# SCREEN.net
KiCad netlist of a schematic drawn in Altium Designer
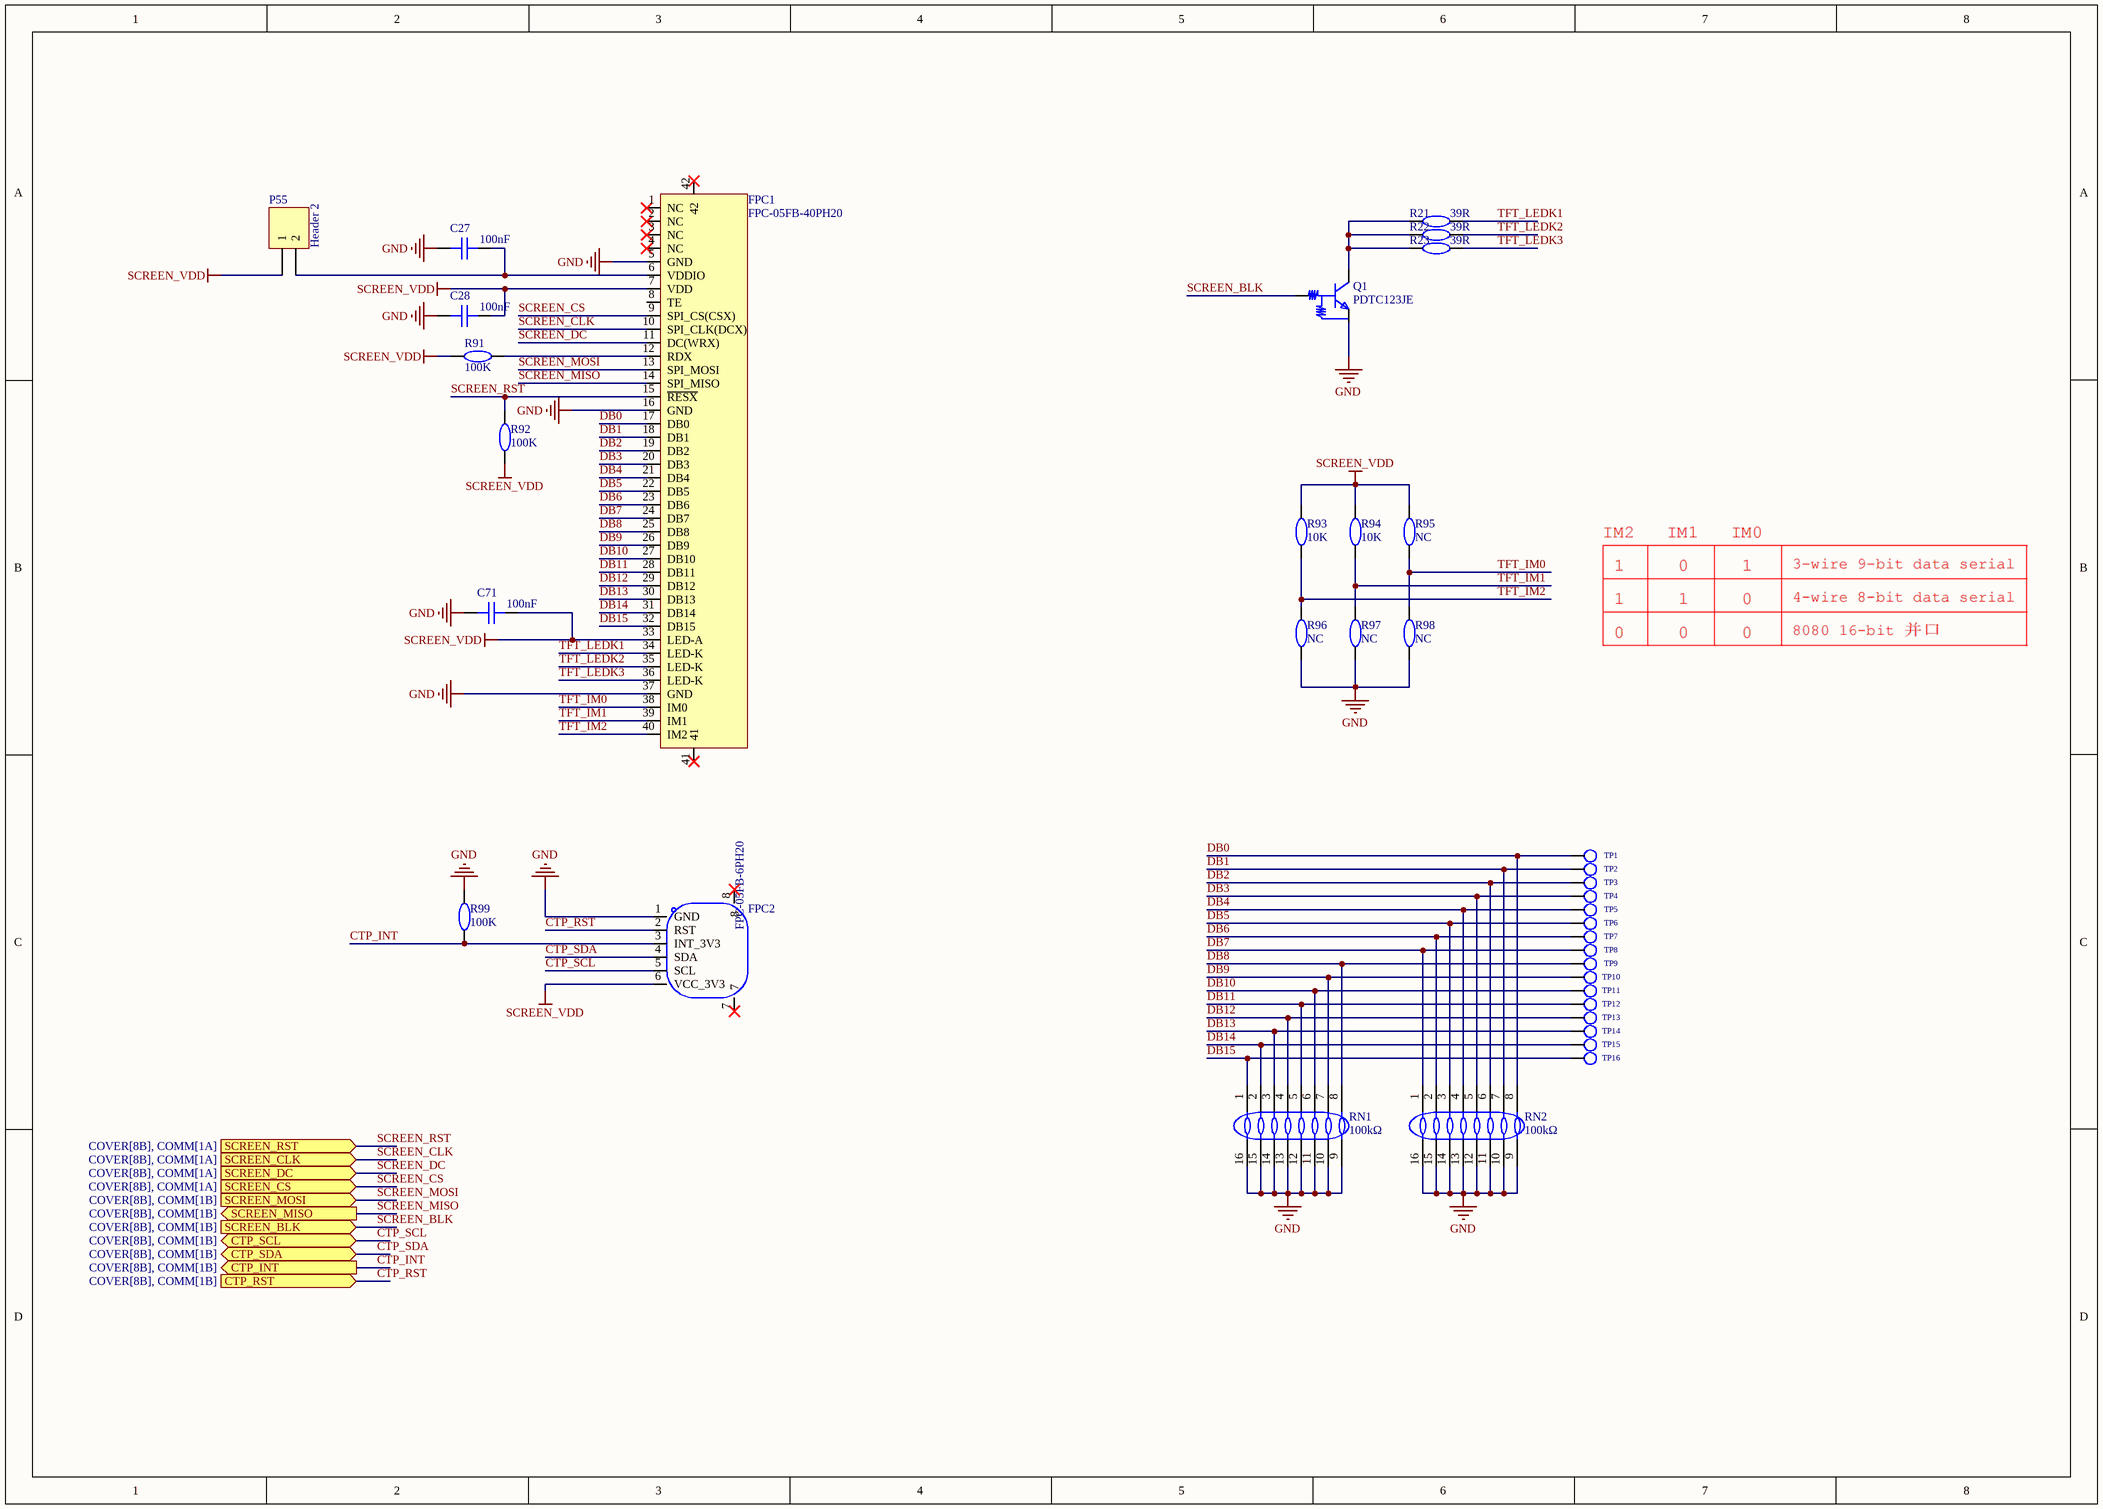
[diagram p0: SCREEN.SchDoc]

(export (version "E")
  (design (tool "Eeschema 10.0.6"))
  (components
    (comp (ref "C27")
      (value "100nF")
      (footprint "C0402")
      (fields (field (name "NAME") "100nF"))
      (libsource (lib "my_library") (part "CAP_0402"))
    )
    (comp (ref "C28")
      (value "100nF")
      (footprint "C0402")
      (fields (field (name "NAME") "100nF"))
      (libsource (lib "my_library") (part "CAP_0402"))
    )
    (comp (ref "C71")
      (value "100nF")
      (footprint "C0402")
      (fields (field (name "NAME") "100nF"))
      (libsource (lib "my_library") (part "CAP_0402"))
    )
    (comp (ref "FPC1")
      (value "FPC-05FB-40PH20")
      (footprint "FPC-SMD_40P-P0.50_XUNPU_FPC-05FB-40PH20")
      (fields (field (name "MANUFACTURER") "XUNPU(讯普)") (field (name "NAME") "FPC-05FB-40PH20"))
      (libsource (lib "my_library") (part "3.2TFT_FPC-05FB-40PH20"))
    )
    (comp (ref "FPC2")
      (value "FPC-05FB-6PH20")
      (footprint "FPC-SMD_6P-P0.50_FPC-05FB-6PH20")
      (fields (field (name "MANUFACTURER") "XUNPU(讯普)") (field (name "NAME") "FPC-05FB-6PH20"))
      (libsource (lib "my_library") (part "3.2TFT_FPC-05FB-6PH20"))
    )
    (comp (ref "P55")
      (value "Header 2")
      (footprint "HDR1X2")
      (description "Header, 2-Pin")
      (fields (field (name "PUBLISHER") "Altium Limited"))
      (libsource (lib "Miscellaneous Connectors") (part "Header 2"))
    )
    (comp (ref "Q1")
      (value "PDTC123JE")
      (footprint "SOT-523_L1.6-W0.8-P1.00-LS1.6-BR")
      (fields (field (name "MANUFACTURER") "Prisemi(芯导)") (field (name "NAME") "PDTC123JE"))
      (libsource (lib "my_library") (part "PDTC123JE"))
    )
    (comp (ref "R21")
      (value "39R")
      (footprint "R0402")
      (fields (field (name "NAME") "39R"))
      (libsource (lib "my_library") (part "Res_0402"))
    )
    (comp (ref "R22")
      (value "39R")
      (footprint "R0402")
      (fields (field (name "NAME") "39R"))
      (libsource (lib "my_library") (part "Res_0402"))
    )
    (comp (ref "R23")
      (value "39R")
      (footprint "R0402")
      (fields (field (name "NAME") "39R"))
      (libsource (lib "my_library") (part "Res_0402"))
    )
    (comp (ref "R91")
      (value "100K")
      (footprint "R0402")
      (fields (field (name "NAME") "100K"))
      (libsource (lib "my_library") (part "Res_0402"))
    )
    (comp (ref "R92")
      (value "100K")
      (footprint "R0402")
      (fields (field (name "NAME") "100K"))
      (libsource (lib "my_library") (part "Res_0402"))
    )
    (comp (ref "R93")
      (value "10K")
      (footprint "R0603")
      (fields (field (name "NAME") "10K"))
      (libsource (lib "my_library") (part "Res_0603"))
    )
    (comp (ref "R94")
      (value "10K")
      (footprint "R0603")
      (fields (field (name "NAME") "10K"))
      (libsource (lib "my_library") (part "Res_0603"))
    )
    (comp (ref "R95")
      (value "NC")
      (footprint "R0603")
      (fields (field (name "NAME") "NC"))
      (libsource (lib "my_library") (part "Res_0603"))
    )
    (comp (ref "R96")
      (value "NC")
      (footprint "R0603")
      (fields (field (name "NAME") "NC"))
      (libsource (lib "my_library") (part "Res_0603"))
    )
    (comp (ref "R97")
      (value "NC")
      (footprint "R0603")
      (fields (field (name "NAME") "NC"))
      (libsource (lib "my_library") (part "Res_0603"))
    )
    (comp (ref "R98")
      (value "NC")
      (footprint "R0603")
      (fields (field (name "NAME") "NC"))
      (libsource (lib "my_library") (part "Res_0603"))
    )
    (comp (ref "R99")
      (value "100K")
      (footprint "R0402")
      (fields (field (name "NAME") "100K"))
      (libsource (lib "my_library") (part "Res_0402"))
    )
    (comp (ref "RN1")
      (value "100kΩ")
      (footprint "RES-ARRAY-SMD_16P-L3.8-W1.6-P0.50-BL")
      (fields
        (field (name "MANUFACTURER") "PANASONIC(松下)")
        (field (name "MANUFACTURER PART") "EXB2HV104JV")
        (field (name "TOLERANCE") "±5%")
        (field (name "NAME") "100kΩ")
      )
      (libsource (lib "my_library") (part "EXB2HV104JV"))
    )
    (comp (ref "RN2")
      (value "100kΩ")
      (footprint "RES-ARRAY-SMD_16P-L3.8-W1.6-P0.50-BL")
      (fields
        (field (name "MANUFACTURER") "PANASONIC(松下)")
        (field (name "MANUFACTURER PART") "EXB2HV104JV")
        (field (name "TOLERANCE") "±5%")
        (field (name "NAME") "100kΩ")
      )
      (libsource (lib "my_library") (part "EXB2HV104JV"))
    )
    (comp (ref "TP1")
      (value "T-SMD")
      (footprint "PAD_1.0_SMT")
      (libsource (lib "my_library") (part "T1.0-SMD"))
    )
    (comp (ref "TP2")
      (value "T-SMD")
      (footprint "PAD_1.0_SMT")
      (libsource (lib "my_library") (part "T1.0-SMD"))
    )
    (comp (ref "TP3")
      (value "T-SMD")
      (footprint "PAD_1.0_SMT")
      (libsource (lib "my_library") (part "T1.0-SMD"))
    )
    (comp (ref "TP4")
      (value "T-SMD")
      (footprint "PAD_1.0_SMT")
      (libsource (lib "my_library") (part "T1.0-SMD"))
    )
    (comp (ref "TP5")
      (value "T-SMD")
      (footprint "PAD_1.0_SMT")
      (libsource (lib "my_library") (part "T1.0-SMD"))
    )
    (comp (ref "TP6")
      (value "T-SMD")
      (footprint "PAD_1.0_SMT")
      (libsource (lib "my_library") (part "T1.0-SMD"))
    )
    (comp (ref "TP7")
      (value "T-SMD")
      (footprint "PAD_1.0_SMT")
      (libsource (lib "my_library") (part "T1.0-SMD"))
    )
    (comp (ref "TP8")
      (value "T-SMD")
      (footprint "PAD_1.0_SMT")
      (libsource (lib "my_library") (part "T1.0-SMD"))
    )
    (comp (ref "TP9")
      (value "T-SMD")
      (footprint "PAD_1.0_SMT")
      (libsource (lib "my_library") (part "T1.0-SMD"))
    )
    (comp (ref "TP10")
      (value "T-SMD")
      (footprint "PAD_1.0_SMT")
      (libsource (lib "my_library") (part "T1.0-SMD"))
    )
    (comp (ref "TP11")
      (value "T-SMD")
      (footprint "PAD_1.0_SMT")
      (libsource (lib "my_library") (part "T1.0-SMD"))
    )
    (comp (ref "TP12")
      (value "T-SMD")
      (footprint "PAD_1.0_SMT")
      (libsource (lib "my_library") (part "T1.0-SMD"))
    )
    (comp (ref "TP13")
      (value "T-SMD")
      (footprint "PAD_1.0_SMT")
      (libsource (lib "my_library") (part "T1.0-SMD"))
    )
    (comp (ref "TP14")
      (value "T-SMD")
      (footprint "PAD_1.0_SMT")
      (libsource (lib "my_library") (part "T1.0-SMD"))
    )
    (comp (ref "TP15")
      (value "T-SMD")
      (footprint "PAD_1.0_SMT")
      (libsource (lib "my_library") (part "T1.0-SMD"))
    )
    (comp (ref "TP16")
      (value "T-SMD")
      (footprint "PAD_1.0_SMT")
      (libsource (lib "my_library") (part "T1.0-SMD"))
    )
  )
  (nets
    (net (code "1") (name "/CTP_INT") (class "Default")
      (node (ref "FPC2") (pin "3") (pinfunction "INT_3V3_3") (pintype "passive"))
      (node (ref "R99") (pin "2") (pinfunction "2_2") (pintype "passive"))
    )
    (net (code "2") (name "/CTP_RST") (class "Default")
      (node (ref "FPC2") (pin "2") (pinfunction "RST_2") (pintype "passive"))
    )
    (net (code "3") (name "/CTP_SCL") (class "Default")
      (node (ref "FPC2") (pin "5") (pinfunction "SCL_5") (pintype "passive"))
    )
    (net (code "4") (name "/CTP_SDA") (class "Default")
      (node (ref "FPC2") (pin "4") (pinfunction "SDA_4") (pintype "passive"))
    )
    (net (code "5") (name "/DB0") (class "Default")
      (node (ref "FPC1") (pin "17") (pinfunction "DB0_17") (pintype "passive"))
      (node (ref "RN2") (pin "8") (pinfunction "8_8") (pintype "passive"))
      (node (ref "TP1") (pin "1") (pinfunction "1_1") (pintype "passive"))
    )
    (net (code "6") (name "/DB1") (class "Default")
      (node (ref "FPC1") (pin "18") (pinfunction "DB1_18") (pintype "passive"))
      (node (ref "RN2") (pin "7") (pinfunction "7_7") (pintype "passive"))
      (node (ref "TP2") (pin "1") (pinfunction "1_1") (pintype "passive"))
    )
    (net (code "7") (name "/DB2") (class "Default")
      (node (ref "FPC1") (pin "19") (pinfunction "DB2_19") (pintype "passive"))
      (node (ref "RN2") (pin "6") (pinfunction "6_6") (pintype "passive"))
      (node (ref "TP3") (pin "1") (pinfunction "1_1") (pintype "passive"))
    )
    (net (code "8") (name "/DB3") (class "Default")
      (node (ref "FPC1") (pin "20") (pinfunction "DB3_20") (pintype "passive"))
      (node (ref "RN2") (pin "5") (pinfunction "5_5") (pintype "passive"))
      (node (ref "TP4") (pin "1") (pinfunction "1_1") (pintype "passive"))
    )
    (net (code "9") (name "/DB4") (class "Default")
      (node (ref "FPC1") (pin "21") (pinfunction "DB4_21") (pintype "passive"))
      (node (ref "RN2") (pin "4") (pinfunction "4_4") (pintype "passive"))
      (node (ref "TP5") (pin "1") (pinfunction "1_1") (pintype "passive"))
    )
    (net (code "10") (name "/DB5") (class "Default")
      (node (ref "FPC1") (pin "22") (pinfunction "DB5_22") (pintype "passive"))
      (node (ref "RN2") (pin "3") (pinfunction "3_3") (pintype "passive"))
      (node (ref "TP6") (pin "1") (pinfunction "1_1") (pintype "passive"))
    )
    (net (code "11") (name "/DB6") (class "Default")
      (node (ref "FPC1") (pin "23") (pinfunction "DB6_23") (pintype "passive"))
      (node (ref "RN2") (pin "2") (pinfunction "2_2") (pintype "passive"))
      (node (ref "TP7") (pin "1") (pinfunction "1_1") (pintype "passive"))
    )
    (net (code "12") (name "/DB7") (class "Default")
      (node (ref "FPC1") (pin "24") (pinfunction "DB7_24") (pintype "passive"))
      (node (ref "RN2") (pin "1") (pinfunction "1_1") (pintype "passive"))
      (node (ref "TP8") (pin "1") (pinfunction "1_1") (pintype "passive"))
    )
    (net (code "13") (name "/DB8") (class "Default")
      (node (ref "FPC1") (pin "25") (pinfunction "DB8_25") (pintype "passive"))
      (node (ref "RN1") (pin "8") (pinfunction "8_8") (pintype "passive"))
      (node (ref "TP9") (pin "1") (pinfunction "1_1") (pintype "passive"))
    )
    (net (code "14") (name "/DB9") (class "Default")
      (node (ref "FPC1") (pin "26") (pinfunction "DB9_26") (pintype "passive"))
      (node (ref "RN1") (pin "7") (pinfunction "7_7") (pintype "passive"))
      (node (ref "TP10") (pin "1") (pinfunction "1_1") (pintype "passive"))
    )
    (net (code "15") (name "/DB10") (class "Default")
      (node (ref "FPC1") (pin "27") (pinfunction "DB10_27") (pintype "passive"))
      (node (ref "RN1") (pin "6") (pinfunction "6_6") (pintype "passive"))
      (node (ref "TP11") (pin "1") (pinfunction "1_1") (pintype "passive"))
    )
    (net (code "16") (name "/DB11") (class "Default")
      (node (ref "FPC1") (pin "28") (pinfunction "DB11_28") (pintype "passive"))
      (node (ref "RN1") (pin "5") (pinfunction "5_5") (pintype "passive"))
      (node (ref "TP12") (pin "1") (pinfunction "1_1") (pintype "passive"))
    )
    (net (code "17") (name "/DB12") (class "Default")
      (node (ref "FPC1") (pin "29") (pinfunction "DB12_29") (pintype "passive"))
      (node (ref "RN1") (pin "4") (pinfunction "4_4") (pintype "passive"))
      (node (ref "TP13") (pin "1") (pinfunction "1_1") (pintype "passive"))
    )
    (net (code "18") (name "/DB13") (class "Default")
      (node (ref "FPC1") (pin "30") (pinfunction "DB13_30") (pintype "passive"))
      (node (ref "RN1") (pin "3") (pinfunction "3_3") (pintype "passive"))
      (node (ref "TP14") (pin "1") (pinfunction "1_1") (pintype "passive"))
    )
    (net (code "19") (name "/DB14") (class "Default")
      (node (ref "FPC1") (pin "31") (pinfunction "DB14_31") (pintype "passive"))
      (node (ref "RN1") (pin "2") (pinfunction "2_2") (pintype "passive"))
      (node (ref "TP15") (pin "1") (pinfunction "1_1") (pintype "passive"))
    )
    (net (code "20") (name "/DB15") (class "Default")
      (node (ref "FPC1") (pin "32") (pinfunction "DB15_32") (pintype "passive"))
      (node (ref "RN1") (pin "1") (pinfunction "1_1") (pintype "passive"))
      (node (ref "TP16") (pin "1") (pinfunction "1_1") (pintype "passive"))
    )
    (net (code "21") (name "/SCREEN_BLK") (class "Default")
      (node (ref "Q1") (pin "1") (pinfunction "IN_1") (pintype "passive"))
    )
    (net (code "22") (name "/SCREEN_CLK") (class "Default")
      (node (ref "FPC1") (pin "10") (pinfunction "SPI_CLK(DCX)_10") (pintype "passive"))
    )
    (net (code "23") (name "/SCREEN_CS") (class "Default")
      (node (ref "FPC1") (pin "9") (pinfunction "SPI_CS(CSX)_9") (pintype "passive"))
    )
    (net (code "24") (name "/SCREEN_DC") (class "Default")
      (node (ref "FPC1") (pin "11") (pinfunction "DC(WRX)_11") (pintype "passive"))
    )
    (net (code "25") (name "/SCREEN_MISO") (class "Default")
      (node (ref "FPC1") (pin "14") (pinfunction "SPI_MISO_14") (pintype "passive"))
    )
    (net (code "26") (name "/SCREEN_MOSI") (class "Default")
      (node (ref "FPC1") (pin "13") (pinfunction "SPI_MOSI_13") (pintype "passive"))
    )
    (net (code "27") (name "/SCREEN_RST") (class "Default")
      (node (ref "FPC1") (pin "15") (pinfunction "~{RESX}_15") (pintype "passive"))
      (node (ref "R92") (pin "2") (pinfunction "2_2") (pintype "passive"))
    )
    (net (code "28") (name "/TFT_IM0") (class "Default")
      (node (ref "FPC1") (pin "38") (pinfunction "IM0_38") (pintype "passive"))
      (node (ref "R95") (pin "1") (pinfunction "1_1") (pintype "passive"))
      (node (ref "R98") (pin "2") (pinfunction "2_2") (pintype "passive"))
    )
    (net (code "29") (name "/TFT_IM1") (class "Default")
      (node (ref "FPC1") (pin "39") (pinfunction "IM1_39") (pintype "passive"))
      (node (ref "R94") (pin "1") (pinfunction "1_1") (pintype "passive"))
      (node (ref "R97") (pin "2") (pinfunction "2_2") (pintype "passive"))
    )
    (net (code "30") (name "/TFT_IM2") (class "Default")
      (node (ref "FPC1") (pin "40") (pinfunction "IM2_40") (pintype "passive"))
      (node (ref "R93") (pin "1") (pinfunction "1_1") (pintype "passive"))
      (node (ref "R96") (pin "2") (pinfunction "2_2") (pintype "passive"))
    )
    (net (code "31") (name "/TFT_LEDK1") (class "Default")
      (node (ref "FPC1") (pin "34") (pinfunction "LED-K_34") (pintype "passive"))
      (node (ref "R21") (pin "2") (pinfunction "2_2") (pintype "passive"))
    )
    (net (code "32") (name "/TFT_LEDK2") (class "Default")
      (node (ref "FPC1") (pin "35") (pinfunction "LED-K_35") (pintype "passive"))
      (node (ref "R22") (pin "2") (pinfunction "2_2") (pintype "passive"))
    )
    (net (code "33") (name "/TFT_LEDK3") (class "Default")
      (node (ref "FPC1") (pin "36") (pinfunction "LED-K_36") (pintype "passive"))
      (node (ref "R23") (pin "2") (pinfunction "2_2") (pintype "passive"))
    )
    (net (code "34") (name "GND") (class "Default")
      (node (ref "C27") (pin "1") (pinfunction "1_1") (pintype "passive"))
      (node (ref "C28") (pin "1") (pinfunction "1_1") (pintype "passive"))
      (node (ref "C71") (pin "1") (pinfunction "1_1") (pintype "passive"))
      (node (ref "FPC1") (pin "16") (pinfunction "GND_16") (pintype "passive"))
      (node (ref "FPC1") (pin "37") (pinfunction "GND_37") (pintype "passive"))
      (node (ref "FPC1") (pin "5") (pinfunction "GND_5") (pintype "passive"))
      (node (ref "FPC2") (pin "1") (pinfunction "GND_1") (pintype "passive"))
      (node (ref "Q1") (pin "2") (pinfunction "GND_2") (pintype "passive"))
      (node (ref "R96") (pin "1") (pinfunction "1_1") (pintype "passive"))
      (node (ref "R97") (pin "1") (pinfunction "1_1") (pintype "passive"))
      (node (ref "R98") (pin "1") (pinfunction "1_1") (pintype "passive"))
      (node (ref "R99") (pin "1") (pinfunction "1_1") (pintype "passive"))
      (node (ref "RN1") (pin "10") (pinfunction "10_10") (pintype "passive"))
      (node (ref "RN1") (pin "11") (pinfunction "11_11") (pintype "passive"))
      (node (ref "RN1") (pin "12") (pinfunction "12_12") (pintype "passive"))
      (node (ref "RN1") (pin "13") (pinfunction "13_13") (pintype "passive"))
      (node (ref "RN1") (pin "14") (pinfunction "14_14") (pintype "passive"))
      (node (ref "RN1") (pin "15") (pinfunction "15_15") (pintype "passive"))
      (node (ref "RN1") (pin "16") (pinfunction "16_16") (pintype "passive"))
      (node (ref "RN1") (pin "9") (pinfunction "9_9") (pintype "passive"))
      (node (ref "RN2") (pin "10") (pinfunction "10_10") (pintype "passive"))
      (node (ref "RN2") (pin "11") (pinfunction "11_11") (pintype "passive"))
      (node (ref "RN2") (pin "12") (pinfunction "12_12") (pintype "passive"))
      (node (ref "RN2") (pin "13") (pinfunction "13_13") (pintype "passive"))
      (node (ref "RN2") (pin "14") (pinfunction "14_14") (pintype "passive"))
      (node (ref "RN2") (pin "15") (pinfunction "15_15") (pintype "passive"))
      (node (ref "RN2") (pin "16") (pinfunction "16_16") (pintype "passive"))
      (node (ref "RN2") (pin "9") (pinfunction "9_9") (pintype "passive"))
    )
    (net (code "35") (name "Net-(FPC1-RDX)") (class "Default")
      (node (ref "FPC1") (pin "12") (pinfunction "RDX_12") (pintype "passive"))
      (node (ref "R91") (pin "2") (pinfunction "2_2") (pintype "passive"))
    )
    (net (code "36") (name "Net-(FPC1-VDDIO)") (class "Default")
      (node (ref "C27") (pin "2") (pinfunction "2_2") (pintype "passive"))
      (node (ref "FPC1") (pin "6") (pinfunction "VDDIO_6") (pintype "passive"))
      (node (ref "P55") (pin "2") (pinfunction "2_2") (pintype "passive"))
    )
    (net (code "37") (name "Net-(Q1-OUT)") (class "Default")
      (node (ref "Q1") (pin "3") (pinfunction "OUT_3") (pintype "passive"))
      (node (ref "R21") (pin "1") (pinfunction "1_1") (pintype "passive"))
      (node (ref "R22") (pin "1") (pinfunction "1_1") (pintype "passive"))
      (node (ref "R23") (pin "1") (pinfunction "1_1") (pintype "passive"))
    )
    (net (code "38") (name "SCREEN_VDD") (class "Default")
      (node (ref "C28") (pin "2") (pinfunction "2_2") (pintype "passive"))
      (node (ref "C71") (pin "2") (pinfunction "2_2") (pintype "passive"))
      (node (ref "FPC1") (pin "33") (pinfunction "LED-A_33") (pintype "passive"))
      (node (ref "FPC1") (pin "7") (pinfunction "VDD_7") (pintype "passive"))
      (node (ref "FPC2") (pin "6") (pinfunction "VCC_3V3_6") (pintype "passive"))
      (node (ref "P55") (pin "1") (pinfunction "1_1") (pintype "passive"))
      (node (ref "R91") (pin "1") (pinfunction "1_1") (pintype "passive"))
      (node (ref "R92") (pin "1") (pinfunction "1_1") (pintype "passive"))
      (node (ref "R93") (pin "2") (pinfunction "2_2") (pintype "passive"))
      (node (ref "R94") (pin "2") (pinfunction "2_2") (pintype "passive"))
      (node (ref "R95") (pin "2") (pinfunction "2_2") (pintype "passive"))
    )
    (net (code "39") (name "unconnected-(FPC1-NC-Pad1)") (class "Default")
      (node (ref "FPC1") (pin "1") (pinfunction "NC_1") (pintype "passive+no_connect"))
    )
    (net (code "40") (name "unconnected-(FPC1-NC-Pad2)") (class "Default")
      (node (ref "FPC1") (pin "2") (pinfunction "NC_2") (pintype "passive+no_connect"))
    )
    (net (code "41") (name "unconnected-(FPC1-NC-Pad3)") (class "Default")
      (node (ref "FPC1") (pin "3") (pinfunction "NC_3") (pintype "passive+no_connect"))
    )
    (net (code "42") (name "unconnected-(FPC1-NC-Pad4)") (class "Default")
      (node (ref "FPC1") (pin "4") (pinfunction "NC_4") (pintype "passive+no_connect"))
    )
    (net (code "43") (name "unconnected-(FPC1-Pad41)") (class "Default")
      (node (ref "FPC1") (pin "41") (pinfunction "41_41") (pintype "passive+no_connect"))
    )
    (net (code "44") (name "unconnected-(FPC1-Pad42)") (class "Default")
      (node (ref "FPC1") (pin "42") (pinfunction "42_42") (pintype "passive+no_connect"))
    )
    (net (code "45") (name "unconnected-(FPC1-TE-Pad8)") (class "Default")
      (node (ref "FPC1") (pin "8") (pinfunction "TE_8") (pintype "passive"))
    )
    (net (code "46") (name "unconnected-(FPC2-Pad7)") (class "Default")
      (node (ref "FPC2") (pin "7") (pinfunction "7_7") (pintype "passive+no_connect"))
    )
    (net (code "47") (name "unconnected-(FPC2-Pad8)") (class "Default")
      (node (ref "FPC2") (pin "8") (pinfunction "8_8") (pintype "passive+no_connect"))
    )
  )
)
